# SmartGarden_SCH.net
KiCad netlist of a schematic drawn in Altium Designer
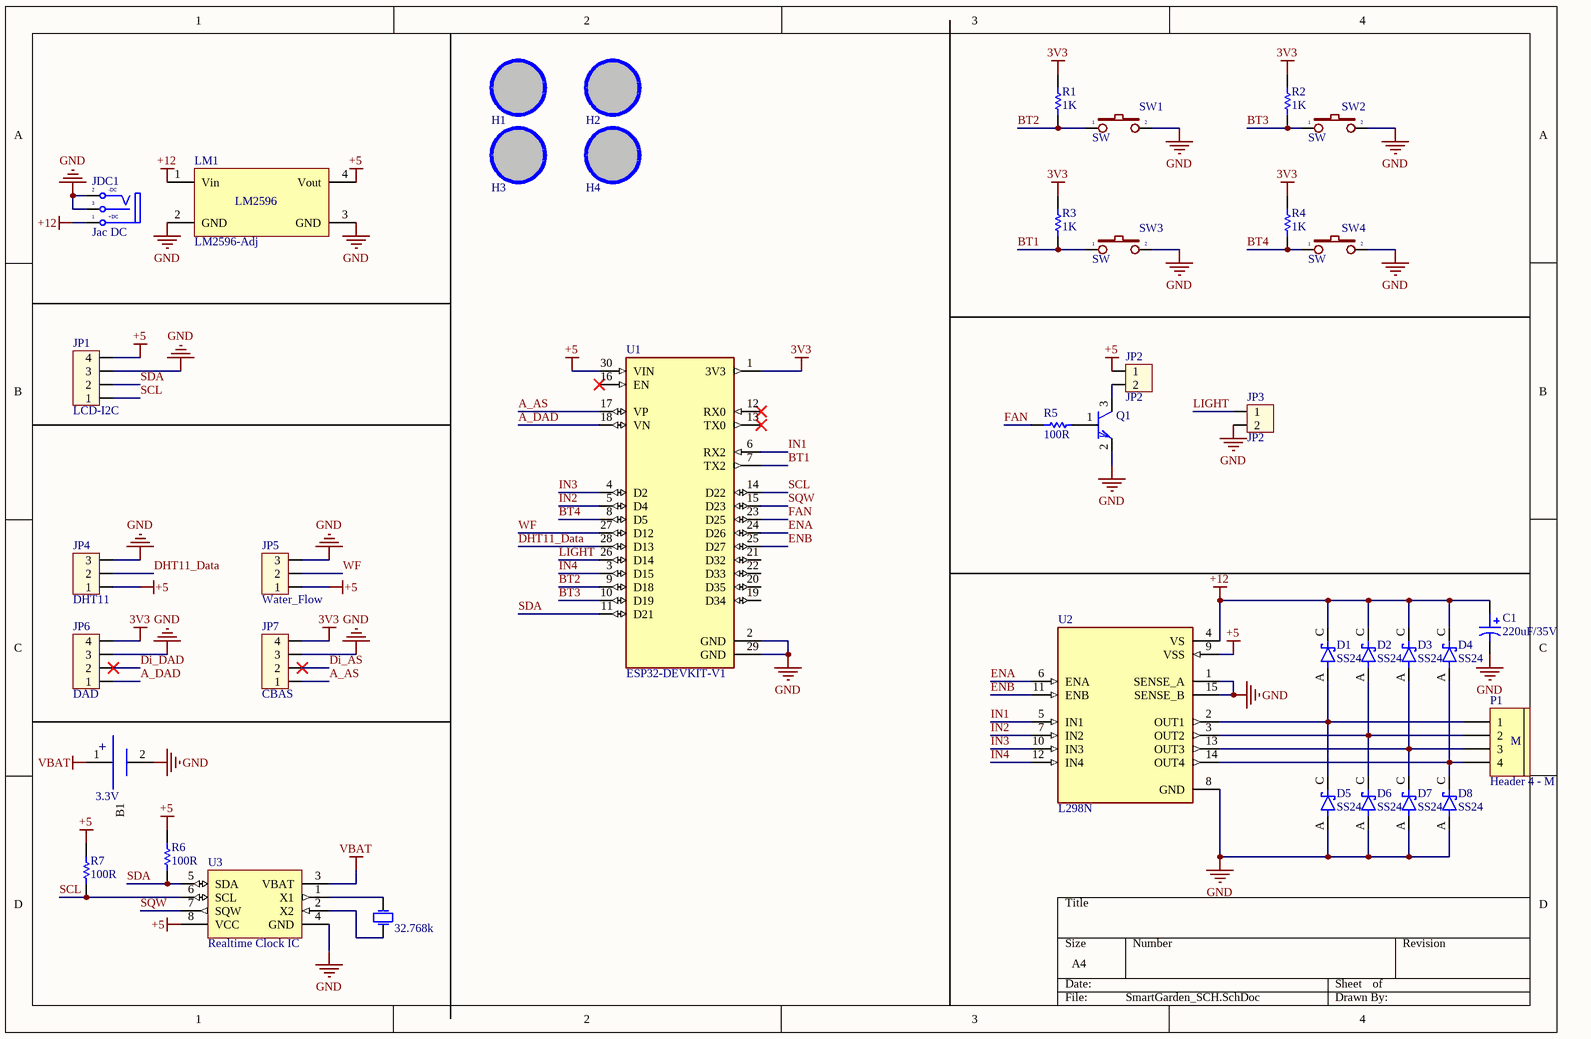
[diagram p0: SmartGarden_SCH.SchDoc]

(export (version "E")
  (design (tool "Eeschema 10.0.6"))
  (components
    (comp (ref "B1")
      (value "3.3V")
      (footprint "BATT-LI-Bott-22mm")
      (description "Battery holder")
      (fields
        (field (name "MANUFACTURER") "China")
        (field (name "Comment") "BATT-Holder")
        (field (name "PUBLISHER") "Hoang Nguyen")
      )
      (libsource (lib "Kiet") (part "BATT-Holder"))
    )
    (comp (ref "C1")
      (value "220uF/35V")
      (footprint "RADIAL E")
      (description "Polarized Capacitor")
      (fields (field (name "Comment") "Cap Pol") (field (name "PUBLISHER") "Altium Limited"))
      (libsource (lib "Kiet") (part "Cap Pol"))
    )
    (comp (ref "D1")
      (value "SS24")
      (footprint "DIOM5336X265N")
      (description "Diode Schottky 40V 2A Surface Mount DO-214AA (SMB)")
      (fields (field (name "MF") "ON Semiconductor"))
      (libsource (lib "SS24") (part "SS24"))
    )
    (comp (ref "D2")
      (value "SS24")
      (footprint "DIOM5336X265N")
      (description "Diode Schottky 40V 2A Surface Mount DO-214AA (SMB)")
      (fields (field (name "MF") "ON Semiconductor"))
      (libsource (lib "SS24") (part "SS24"))
    )
    (comp (ref "D3")
      (value "SS24")
      (footprint "DIOM5336X265N")
      (description "Diode Schottky 40V 2A Surface Mount DO-214AA (SMB)")
      (fields (field (name "MF") "ON Semiconductor"))
      (libsource (lib "SS24") (part "SS24"))
    )
    (comp (ref "D4")
      (value "SS24")
      (footprint "DIOM5336X265N")
      (description "Diode Schottky 40V 2A Surface Mount DO-214AA (SMB)")
      (fields (field (name "MF") "ON Semiconductor"))
      (libsource (lib "SS24") (part "SS24"))
    )
    (comp (ref "D5")
      (value "SS24")
      (footprint "DIOM5336X265N")
      (description "Diode Schottky 40V 2A Surface Mount DO-214AA (SMB)")
      (fields (field (name "MF") "ON Semiconductor"))
      (libsource (lib "SS24") (part "SS24"))
    )
    (comp (ref "D6")
      (value "SS24")
      (footprint "DIOM5336X265N")
      (description "Diode Schottky 40V 2A Surface Mount DO-214AA (SMB)")
      (fields (field (name "MF") "ON Semiconductor"))
      (libsource (lib "SS24") (part "SS24"))
    )
    (comp (ref "D7")
      (value "SS24")
      (footprint "DIOM5336X265N")
      (description "Diode Schottky 40V 2A Surface Mount DO-214AA (SMB)")
      (fields (field (name "MF") "ON Semiconductor"))
      (libsource (lib "SS24") (part "SS24"))
    )
    (comp (ref "D8")
      (value "SS24")
      (footprint "DIOM5336X265N")
      (description "Diode Schottky 40V 2A Surface Mount DO-214AA (SMB)")
      (fields (field (name "MF") "ON Semiconductor"))
      (libsource (lib "SS24") (part "SS24"))
    )
    (comp (ref "H1")
      (value "Hole")
      (footprint "LO KHOAN 3MM")
      (description "Hole 3mm")
      (libsource (lib "thuvienhoang") (part "Hole"))
    )
    (comp (ref "H2")
      (value "Hole")
      (footprint "LO KHOAN 3MM")
      (description "Hole 3mm")
      (libsource (lib "thuvienhoang") (part "Hole"))
    )
    (comp (ref "H3")
      (value "Hole")
      (footprint "LO KHOAN 3MM")
      (description "Hole 3mm")
      (libsource (lib "thuvienhoang") (part "Hole"))
    )
    (comp (ref "H4")
      (value "Hole")
      (footprint "LO KHOAN 3MM")
      (description "Hole 3mm")
      (libsource (lib "thuvienhoang") (part "Hole"))
    )
    (comp (ref "JDC1")
      (value "Jac DC")
      (footprint "DC-IN")
      (description "Jac DC input")
      (libsource (lib "Kiet") (part "DCIN"))
    )
    (comp (ref "JP1")
      (value "LCD-I2C")
      (footprint "CON4")
      (description "Connector 4")
      (libsource (lib "Kiet") (part "Con4"))
    )
    (comp (ref "JP2")
      (value "JP2")
      (footprint "CON2")
      (description "Connector 2")
      (libsource (lib "Kiet") (part "Con2"))
    )
    (comp (ref "JP3")
      (value "JP2")
      (footprint "CON2")
      (description "Connector 2")
      (libsource (lib "Kiet") (part "Con2"))
    )
    (comp (ref "JP4")
      (value "DHT11")
      (footprint "CON3")
      (description "Connector 3")
      (libsource (lib "Kiet") (part "Con3"))
    )
    (comp (ref "JP5")
      (value "Water_Flow")
      (footprint "CON3")
      (description "Connector 3")
      (libsource (lib "Kiet") (part "Con3"))
    )
    (comp (ref "JP6")
      (value "DAD")
      (footprint "CON4")
      (description "Connector 4")
      (libsource (lib "Kiet") (part "Con4"))
    )
    (comp (ref "JP7")
      (value "CBAS")
      (footprint "CON4")
      (description "Connector 4")
      (libsource (lib "Kiet") (part "Con4"))
    )
    (comp (ref "LM1")
      (value "LM2596-Adj")
      (footprint "lm2596")
      (description "Designed By @Alixahedi")
      (libsource (lib "LM2596-Adj") (part "LM2596-Adj"))
    )
    (comp (ref "P1")
      (value "Header 4 - M")
      (footprint "Medium - Header 4")
      (description "Header, 3-Pin, Medium")
      (fields (field (name "PUBLISHER") "Altium Limited"))
      (libsource (lib "Kiet") (part "Header 4 - M"))
    )
    (comp (ref "Q1")
      (value "C1815")
      (footprint "SOT23 [C1815]")
      (description "Q2SC1815")
      (fields (field (name "PUBLISHER") "Hoang Nguyen"))
      (libsource (lib "Kiet") (part "C1815"))
    )
    (comp (ref "R1")
      (value "1K")
      (footprint "R-0805")
      (description "Resistor")
      (fields (field (name "Comment") "RESISTOR") (field (name "PUBLISHER") "Altium Limited"))
      (libsource (lib "Kiet") (part "RESISTOR"))
    )
    (comp (ref "R2")
      (value "1K")
      (footprint "R-0805")
      (description "Resistor")
      (fields (field (name "Comment") "RESISTOR") (field (name "PUBLISHER") "Altium Limited"))
      (libsource (lib "Kiet") (part "RESISTOR"))
    )
    (comp (ref "R3")
      (value "1K")
      (footprint "R-0805")
      (description "Resistor")
      (fields (field (name "Comment") "RESISTOR") (field (name "PUBLISHER") "Altium Limited"))
      (libsource (lib "Kiet") (part "RESISTOR"))
    )
    (comp (ref "R4")
      (value "1K")
      (footprint "R-0805")
      (description "Resistor")
      (fields (field (name "Comment") "RESISTOR") (field (name "PUBLISHER") "Altium Limited"))
      (libsource (lib "Kiet") (part "RESISTOR"))
    )
    (comp (ref "R5")
      (value "100R")
      (footprint "R-0805")
      (description "Resistor")
      (fields (field (name "Comment") "RESISTOR") (field (name "PUBLISHER") "Altium Limited"))
      (libsource (lib "Kiet") (part "RESISTOR"))
    )
    (comp (ref "R6")
      (value "100R")
      (footprint "R-0805")
      (description "Resistor")
      (fields (field (name "Comment") "RESISTOR") (field (name "PUBLISHER") "Altium Limited"))
      (libsource (lib "Kiet") (part "RESISTOR"))
    )
    (comp (ref "R7")
      (value "100R")
      (footprint "R-0805")
      (description "Resistor")
      (fields (field (name "Comment") "RESISTOR") (field (name "PUBLISHER") "Altium Limited"))
      (libsource (lib "Kiet") (part "RESISTOR"))
    )
    (comp (ref "SW1")
      (value "SW")
      (footprint "SW2")
      (description "Switch button 2 pin")
      (libsource (lib "Kiet") (part "SW2"))
    )
    (comp (ref "SW2")
      (value "SW")
      (footprint "SW2")
      (description "Switch button 2 pin")
      (libsource (lib "Kiet") (part "SW2"))
    )
    (comp (ref "SW3")
      (value "SW")
      (footprint "SW2")
      (description "Switch button 2 pin")
      (libsource (lib "Kiet") (part "SW2"))
    )
    (comp (ref "SW4")
      (value "SW")
      (footprint "SW2")
      (description "Switch button 2 pin")
      (libsource (lib "Kiet") (part "SW2"))
    )
    (comp (ref "U1")
      (value "ESP32-DEVKIT-V1")
      (footprint "MODULE_ESP32_DEVKIT_V1")
      (fields (field (name "MF") "Do it"))
      (libsource (lib "ESP32-DEVKIT-V1") (part "ESP32-DEVKIT-V1"))
    )
    (comp (ref "U2")
      (value "L298N")
      (footprint "TO127P2020X500X2100-15")
      (description "Dual Full Bridge Motor Driver 15-Pin(15+Tab) MULTIWATT V Tube")
      (libsource (lib "L298N") (part "L298N"))
    )
    (comp (ref "U3")
      (value "Realtime Clock IC")
      (footprint "DS1307.Dip8")
      (fields (field (name "MANUFACTURER") "Maxim"))
      (libsource (lib "Kiet") (part "DS1307"))
    )
    (comp (ref "Y1")
      (value "32.768k")
      (footprint "XT32kn")
      (description "Crystal Oscillator")
      (fields (field (name "PUBLISHER") "Altium Limited"))
      (libsource (lib "thuvienhoang") (part "Crystal"))
    )
  )
  (nets
    (net (code "1") (name "+5") (class "Default")
      (node (ref "JP1") (pin "4") (pinfunction "4_4") (pintype "passive"))
      (node (ref "JP2") (pin "1") (pinfunction "1_1") (pintype "passive"))
      (node (ref "JP4") (pin "1") (pinfunction "1_1") (pintype "passive"))
      (node (ref "JP5") (pin "1") (pinfunction "1_1") (pintype "passive"))
      (node (ref "LM1") (pin "4") (pinfunction "Vout_4") (pintype "passive"))
      (node (ref "R6") (pin "1") (pinfunction "1_1") (pintype "passive"))
      (node (ref "R7") (pin "1") (pinfunction "1_1") (pintype "passive"))
      (node (ref "U1") (pin "30") (pinfunction "VIN_30") (pintype "input"))
      (node (ref "U2") (pin "9") (pinfunction "VSS_9") (pintype "input"))
      (node (ref "U3") (pin "8") (pinfunction "VCC_8") (pintype "power_in"))
    )
    (net (code "2") (name "+12") (class "Default")
      (node (ref "C1") (pin "1") (pinfunction "1_1") (pintype "passive"))
      (node (ref "D1") (pin "C") (pinfunction "K_C") (pintype "passive"))
      (node (ref "D2") (pin "C") (pinfunction "K_C") (pintype "passive"))
      (node (ref "D3") (pin "C") (pinfunction "K_C") (pintype "passive"))
      (node (ref "D4") (pin "C") (pinfunction "K_C") (pintype "passive"))
      (node (ref "JDC1") (pin "1") (pinfunction "T_1") (pintype "passive"))
      (node (ref "LM1") (pin "1") (pinfunction "Vin_1") (pintype "passive"))
      (node (ref "U2") (pin "4") (pinfunction "VS_4") (pintype "power_in"))
    )
    (net (code "3") (name "/A_AS") (class "Default")
      (node (ref "JP7") (pin "1") (pinfunction "1_1") (pintype "passive"))
      (node (ref "U1") (pin "17") (pinfunction "VP_17") (pintype "bidirectional"))
    )
    (net (code "4") (name "/A_DAD") (class "Default")
      (node (ref "JP6") (pin "1") (pinfunction "1_1") (pintype "passive"))
      (node (ref "U1") (pin "18") (pinfunction "VN_18") (pintype "bidirectional"))
    )
    (net (code "5") (name "/BT1") (class "Default")
      (node (ref "R3") (pin "1") (pinfunction "1_1") (pintype "passive"))
      (node (ref "SW3") (pin "1") (pinfunction "1_1") (pintype "passive"))
      (node (ref "U1") (pin "7") (pinfunction "TX2_7") (pintype "output"))
    )
    (net (code "6") (name "/BT2") (class "Default")
      (node (ref "R1") (pin "1") (pinfunction "1_1") (pintype "passive"))
      (node (ref "SW1") (pin "1") (pinfunction "1_1") (pintype "passive"))
      (node (ref "U1") (pin "9") (pinfunction "D18_9") (pintype "bidirectional"))
    )
    (net (code "7") (name "/BT3") (class "Default")
      (node (ref "R2") (pin "1") (pinfunction "1_1") (pintype "passive"))
      (node (ref "SW2") (pin "1") (pinfunction "1_1") (pintype "passive"))
      (node (ref "U1") (pin "10") (pinfunction "D19_10") (pintype "bidirectional"))
    )
    (net (code "8") (name "/BT4") (class "Default")
      (node (ref "R4") (pin "1") (pinfunction "1_1") (pintype "passive"))
      (node (ref "SW4") (pin "1") (pinfunction "1_1") (pintype "passive"))
      (node (ref "U1") (pin "8") (pinfunction "D5_8") (pintype "bidirectional"))
    )
    (net (code "9") (name "/DHT11_Data") (class "Default")
      (node (ref "JP4") (pin "2") (pinfunction "2_2") (pintype "passive"))
      (node (ref "U1") (pin "28") (pinfunction "D13_28") (pintype "bidirectional"))
    )
    (net (code "10") (name "/Di_AS") (class "Default")
      (node (ref "JP7") (pin "2") (pinfunction "2_2") (pintype "passive+no_connect"))
    )
    (net (code "11") (name "/Di_DAD") (class "Default")
      (node (ref "JP6") (pin "2") (pinfunction "2_2") (pintype "passive+no_connect"))
    )
    (net (code "12") (name "/ENA") (class "Default")
      (node (ref "U1") (pin "24") (pinfunction "D26_24") (pintype "bidirectional"))
      (node (ref "U2") (pin "6") (pinfunction "ENA_6") (pintype "input"))
    )
    (net (code "13") (name "/ENB") (class "Default")
      (node (ref "U1") (pin "25") (pinfunction "D27_25") (pintype "bidirectional"))
      (node (ref "U2") (pin "11") (pinfunction "ENB_11") (pintype "input"))
    )
    (net (code "14") (name "/FAN") (class "Default")
      (node (ref "R5") (pin "2") (pinfunction "2_2") (pintype "passive"))
      (node (ref "U1") (pin "23") (pinfunction "D25_23") (pintype "bidirectional"))
    )
    (net (code "15") (name "/IN1") (class "Default")
      (node (ref "U1") (pin "6") (pinfunction "RX2_6") (pintype "input"))
      (node (ref "U2") (pin "5") (pinfunction "IN1_5") (pintype "input"))
    )
    (net (code "16") (name "/IN2") (class "Default")
      (node (ref "U1") (pin "5") (pinfunction "D4_5") (pintype "bidirectional"))
      (node (ref "U2") (pin "7") (pinfunction "IN2_7") (pintype "input"))
    )
    (net (code "17") (name "/IN3") (class "Default")
      (node (ref "U1") (pin "4") (pinfunction "D2_4") (pintype "bidirectional"))
      (node (ref "U2") (pin "10") (pinfunction "IN3_10") (pintype "input"))
    )
    (net (code "18") (name "/IN4") (class "Default")
      (node (ref "U1") (pin "3") (pinfunction "D15_3") (pintype "bidirectional"))
      (node (ref "U2") (pin "12") (pinfunction "IN4_12") (pintype "input"))
    )
    (net (code "19") (name "/LIGHT") (class "Default")
      (node (ref "JP3") (pin "1") (pinfunction "1_1") (pintype "passive"))
      (node (ref "U1") (pin "26") (pinfunction "D14_26") (pintype "bidirectional"))
    )
    (net (code "20") (name "/SCL") (class "Default")
      (node (ref "JP1") (pin "1") (pinfunction "1_1") (pintype "passive"))
      (node (ref "R7") (pin "2") (pinfunction "2_2") (pintype "passive"))
      (node (ref "U1") (pin "14") (pinfunction "D22_14") (pintype "bidirectional"))
      (node (ref "U3") (pin "6") (pinfunction "SCL_6") (pintype "bidirectional"))
    )
    (net (code "21") (name "/SDA") (class "Default")
      (node (ref "JP1") (pin "2") (pinfunction "2_2") (pintype "passive"))
      (node (ref "R6") (pin "2") (pinfunction "2_2") (pintype "passive"))
      (node (ref "U1") (pin "11") (pinfunction "D21_11") (pintype "bidirectional"))
      (node (ref "U3") (pin "5") (pinfunction "SDA_5") (pintype "bidirectional"))
    )
    (net (code "22") (name "/SQW") (class "Default")
      (node (ref "U1") (pin "15") (pinfunction "D23_15") (pintype "bidirectional"))
      (node (ref "U3") (pin "7") (pinfunction "SQW_7") (pintype "output"))
    )
    (net (code "23") (name "/WF") (class "Default")
      (node (ref "JP5") (pin "2") (pinfunction "2_2") (pintype "passive"))
      (node (ref "U1") (pin "27") (pinfunction "D12_27") (pintype "bidirectional"))
    )
    (net (code "24") (name "3V3") (class "Default")
      (node (ref "JP6") (pin "4") (pinfunction "4_4") (pintype "passive"))
      (node (ref "JP7") (pin "4") (pinfunction "4_4") (pintype "passive"))
      (node (ref "R1") (pin "2") (pinfunction "2_2") (pintype "passive"))
      (node (ref "R2") (pin "2") (pinfunction "2_2") (pintype "passive"))
      (node (ref "R3") (pin "2") (pinfunction "2_2") (pintype "passive"))
      (node (ref "R4") (pin "2") (pinfunction "2_2") (pintype "passive"))
      (node (ref "U1") (pin "1") (pinfunction "3V3_1") (pintype "output"))
    )
    (net (code "25") (name "GND") (class "Default")
      (node (ref "B1") (pin "2") (pinfunction "-_2") (pintype "passive"))
      (node (ref "C1") (pin "2") (pinfunction "2_2") (pintype "passive"))
      (node (ref "D5") (pin "A") (pinfunction "A_A") (pintype "passive"))
      (node (ref "D6") (pin "A") (pinfunction "A_A") (pintype "passive"))
      (node (ref "D7") (pin "A") (pinfunction "A_A") (pintype "passive"))
      (node (ref "D8") (pin "A") (pinfunction "A_A") (pintype "passive"))
      (node (ref "JDC1") (pin "2") (pinfunction "TN_2") (pintype "passive"))
      (node (ref "JDC1") (pin "3") (pinfunction "S_3") (pintype "power_in"))
      (node (ref "JP1") (pin "3") (pinfunction "3_3") (pintype "passive"))
      (node (ref "JP3") (pin "2") (pinfunction "2_2") (pintype "passive"))
      (node (ref "JP4") (pin "3") (pinfunction "3_3") (pintype "passive"))
      (node (ref "JP5") (pin "3") (pinfunction "3_3") (pintype "passive"))
      (node (ref "JP6") (pin "3") (pinfunction "3_3") (pintype "passive"))
      (node (ref "JP7") (pin "3") (pinfunction "3_3") (pintype "passive"))
      (node (ref "LM1") (pin "2") (pinfunction "GND_2") (pintype "passive"))
      (node (ref "LM1") (pin "3") (pinfunction "GND_3") (pintype "passive"))
      (node (ref "Q1") (pin "2") (pinfunction "E_2") (pintype "passive"))
      (node (ref "SW1") (pin "2") (pinfunction "2_2") (pintype "passive"))
      (node (ref "SW2") (pin "2") (pinfunction "2_2") (pintype "passive"))
      (node (ref "SW3") (pin "2") (pinfunction "2_2") (pintype "passive"))
      (node (ref "SW4") (pin "2") (pinfunction "2_2") (pintype "passive"))
      (node (ref "U1") (pin "2") (pinfunction "GND_2") (pintype "power_in"))
      (node (ref "U1") (pin "29") (pinfunction "GND_29") (pintype "power_in"))
      (node (ref "U2") (pin "1") (pinfunction "SENSE_A_1") (pintype "passive"))
      (node (ref "U2") (pin "15") (pinfunction "SENSE_B_15") (pintype "passive"))
      (node (ref "U2") (pin "8") (pinfunction "GND_8") (pintype "power_in"))
      (node (ref "U3") (pin "4") (pinfunction "GND_4") (pintype "power_in"))
    )
    (net (code "26") (name "Net-(D5-K)") (class "Default")
      (node (ref "D1") (pin "A") (pinfunction "A_A") (pintype "passive"))
      (node (ref "D5") (pin "C") (pinfunction "K_C") (pintype "passive"))
      (node (ref "P1") (pin "1") (pinfunction "1_1") (pintype "passive"))
      (node (ref "U2") (pin "2") (pinfunction "OUT1_2") (pintype "output"))
    )
    (net (code "27") (name "Net-(D6-K)") (class "Default")
      (node (ref "D2") (pin "A") (pinfunction "A_A") (pintype "passive"))
      (node (ref "D6") (pin "C") (pinfunction "K_C") (pintype "passive"))
      (node (ref "P1") (pin "2") (pinfunction "2_2") (pintype "passive"))
      (node (ref "U2") (pin "3") (pinfunction "OUT2_3") (pintype "output"))
    )
    (net (code "28") (name "Net-(D7-K)") (class "Default")
      (node (ref "D3") (pin "A") (pinfunction "A_A") (pintype "passive"))
      (node (ref "D7") (pin "C") (pinfunction "K_C") (pintype "passive"))
      (node (ref "P1") (pin "3") (pinfunction "3_3") (pintype "passive"))
      (node (ref "U2") (pin "13") (pinfunction "OUT3_13") (pintype "output"))
    )
    (net (code "29") (name "Net-(D8-K)") (class "Default")
      (node (ref "D4") (pin "A") (pinfunction "A_A") (pintype "passive"))
      (node (ref "D8") (pin "C") (pinfunction "K_C") (pintype "passive"))
      (node (ref "P1") (pin "4") (pinfunction "4_4") (pintype "passive"))
      (node (ref "U2") (pin "14") (pinfunction "OUT4_14") (pintype "output"))
    )
    (net (code "30") (name "Net-(Q1-B)") (class "Default")
      (node (ref "Q1") (pin "1") (pinfunction "B_1") (pintype "passive"))
      (node (ref "R5") (pin "1") (pinfunction "1_1") (pintype "passive"))
    )
    (net (code "31") (name "Net-(Q1-C)") (class "Default")
      (node (ref "JP2") (pin "2") (pinfunction "2_2") (pintype "passive"))
      (node (ref "Q1") (pin "3") (pinfunction "C_3") (pintype "passive"))
    )
    (net (code "32") (name "Net-(U3-X1)") (class "Default")
      (node (ref "U3") (pin "1") (pinfunction "X1_1") (pintype "output"))
      (node (ref "Y1") (pin "2") (pinfunction "OSC2_2") (pintype "passive"))
    )
    (net (code "33") (name "Net-(U3-X2)") (class "Default")
      (node (ref "U3") (pin "2") (pinfunction "X2_2") (pintype "input"))
      (node (ref "Y1") (pin "1") (pinfunction "OSC1_1") (pintype "passive"))
    )
    (net (code "34") (name "VBAT") (class "Default")
      (node (ref "B1") (pin "1") (pinfunction "+_1") (pintype "passive"))
      (node (ref "U3") (pin "3") (pinfunction "VBAT_3") (pintype "power_in"))
    )
    (net (code "35") (name "unconnected-(H1-Pad1)") (class "Default")
      (node (ref "H1") (pin "1") (pinfunction "1_1") (pintype "passive"))
    )
    (net (code "36") (name "unconnected-(H2-Pad1)") (class "Default")
      (node (ref "H2") (pin "1") (pinfunction "1_1") (pintype "passive"))
    )
    (net (code "37") (name "unconnected-(H3-Pad1)") (class "Default")
      (node (ref "H3") (pin "1") (pinfunction "1_1") (pintype "passive"))
    )
    (net (code "38") (name "unconnected-(H4-Pad1)") (class "Default")
      (node (ref "H4") (pin "1") (pinfunction "1_1") (pintype "passive"))
    )
    (net (code "39") (name "unconnected-(U1-D32-Pad21)") (class "Default")
      (node (ref "U1") (pin "21") (pinfunction "D32_21") (pintype "bidirectional"))
    )
    (net (code "40") (name "unconnected-(U1-D33-Pad22)") (class "Default")
      (node (ref "U1") (pin "22") (pinfunction "D33_22") (pintype "bidirectional"))
    )
    (net (code "41") (name "unconnected-(U1-D34-Pad19)") (class "Default")
      (node (ref "U1") (pin "19") (pinfunction "D34_19") (pintype "bidirectional"))
    )
    (net (code "42") (name "unconnected-(U1-D35-Pad20)") (class "Default")
      (node (ref "U1") (pin "20") (pinfunction "D35_20") (pintype "bidirectional"))
    )
    (net (code "43") (name "unconnected-(U1-EN-Pad16)") (class "Default")
      (node (ref "U1") (pin "16") (pinfunction "EN_16") (pintype "input+no_connect"))
    )
    (net (code "44") (name "unconnected-(U1-RX0-Pad12)") (class "Default")
      (node (ref "U1") (pin "12") (pinfunction "RX0_12") (pintype "input+no_connect"))
    )
    (net (code "45") (name "unconnected-(U1-TX0-Pad13)") (class "Default")
      (node (ref "U1") (pin "13") (pinfunction "TX0_13") (pintype "output+no_connect"))
    )
  )
)
